# FLASH.net
KiCad netlist of a schematic drawn in Altium Designer
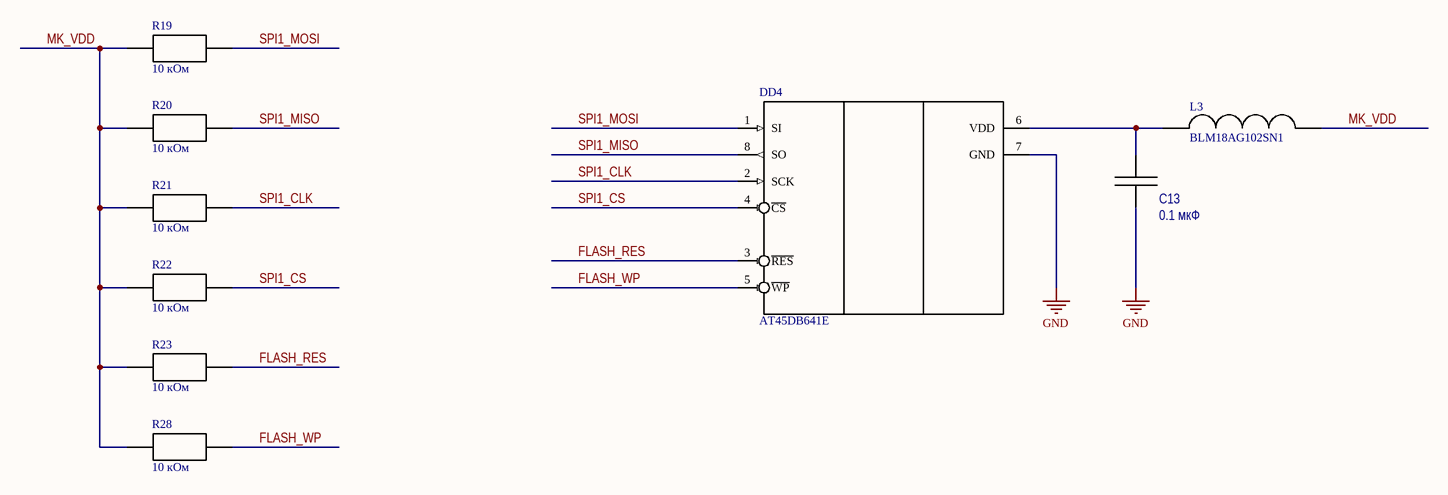
[diagram p0: FLASH.SchDoc]

(export (version "E")
  (design (tool "Eeschema 10.0.6"))
  (components
    (comp (ref "C13")
      (value "0.1 мкФ")
      (footprint "C 1206")
      (description "SMD Capacitor 1206")
      (fields
        (field (name "TOLERANCE") "/Укажите допуск в процентах/")
        (field (name "MANUFACTURER") "/Укажите компанию-производителя/")
      )
      (libsource (lib "my_lib") (part "CAP 1206"))
    )
    (comp (ref "DD4")
      (value "AT45DB641E")
      (footprint "SOIC127P800X216-8N")
      (libsource (lib "my_lib") (part "AT45DB641E"))
    )
    (comp (ref "L3")
      (value "BLM18AG102SN1")
      (footprint "FB 0603")
      (libsource (lib "my_lib") (part "BLM18AG102SN1"))
    )
    (comp (ref "R19") (value "10 кОм") (footprint "RES 0805") (libsource (lib "my_lib") (part "RES 0805")))
    (comp (ref "R20") (value "10 кОм") (footprint "RES 0805") (libsource (lib "my_lib") (part "RES 0805")))
    (comp (ref "R21") (value "10 кОм") (footprint "RES 0805") (libsource (lib "my_lib") (part "RES 0805")))
    (comp (ref "R22") (value "10 кОм") (footprint "RES 0805") (libsource (lib "my_lib") (part "RES 0805")))
    (comp (ref "R23") (value "10 кОм") (footprint "RES 0805") (libsource (lib "my_lib") (part "RES 0805")))
    (comp (ref "R28") (value "10 кОм") (footprint "RES 0805") (libsource (lib "my_lib") (part "RES 0805")))
  )
  (nets
    (net (code "1") (name "/FLASH_RES") (class "Default")
      (node (ref "DD4") (pin "3") (pinfunction "~{RES}_3") (pintype "input"))
      (node (ref "R23") (pin "2") (pinfunction "2_2") (pintype "passive"))
    )
    (net (code "2") (name "/FLASH_WP") (class "Default")
      (node (ref "DD4") (pin "5") (pinfunction "~{WP}_5") (pintype "input"))
      (node (ref "R28") (pin "2") (pinfunction "2_2") (pintype "passive"))
    )
    (net (code "3") (name "/MK_VDD") (class "Default")
      (node (ref "L3") (pin "2") (pinfunction "2_2") (pintype "passive"))
      (node (ref "R19") (pin "1") (pinfunction "1_1") (pintype "passive"))
      (node (ref "R20") (pin "1") (pinfunction "1_1") (pintype "passive"))
      (node (ref "R21") (pin "1") (pinfunction "1_1") (pintype "passive"))
      (node (ref "R22") (pin "1") (pinfunction "1_1") (pintype "passive"))
      (node (ref "R23") (pin "1") (pinfunction "1_1") (pintype "passive"))
      (node (ref "R28") (pin "1") (pinfunction "1_1") (pintype "passive"))
    )
    (net (code "4") (name "/SPI1_CLK") (class "Default")
      (node (ref "DD4") (pin "2") (pinfunction "SCK_2") (pintype "input"))
      (node (ref "R21") (pin "2") (pinfunction "2_2") (pintype "passive"))
    )
    (net (code "5") (name "/SPI1_CS") (class "Default")
      (node (ref "DD4") (pin "4") (pinfunction "~{CS}_4") (pintype "input"))
      (node (ref "R22") (pin "2") (pinfunction "2_2") (pintype "passive"))
    )
    (net (code "6") (name "/SPI1_MISO") (class "Default")
      (node (ref "DD4") (pin "8") (pinfunction "SO_8") (pintype "output"))
      (node (ref "R20") (pin "2") (pinfunction "2_2") (pintype "passive"))
    )
    (net (code "7") (name "/SPI1_MOSI") (class "Default")
      (node (ref "DD4") (pin "1") (pinfunction "SI_1") (pintype "input"))
      (node (ref "R19") (pin "2") (pinfunction "2_2") (pintype "passive"))
    )
    (net (code "8") (name "GND") (class "Default")
      (node (ref "C13") (pin "2") (pinfunction "2_2") (pintype "passive"))
      (node (ref "DD4") (pin "7") (pinfunction "GND_7") (pintype "power_in"))
    )
    (net (code "9") (name "Net-(DD4-VDD)") (class "Default")
      (node (ref "C13") (pin "1") (pinfunction "1_1") (pintype "passive"))
      (node (ref "DD4") (pin "6") (pinfunction "VDD_6") (pintype "power_in"))
      (node (ref "L3") (pin "1") (pinfunction "1_1") (pintype "passive"))
    )
  )
)
